# Controller.net
KiCad netlist of a schematic drawn in Altium Designer
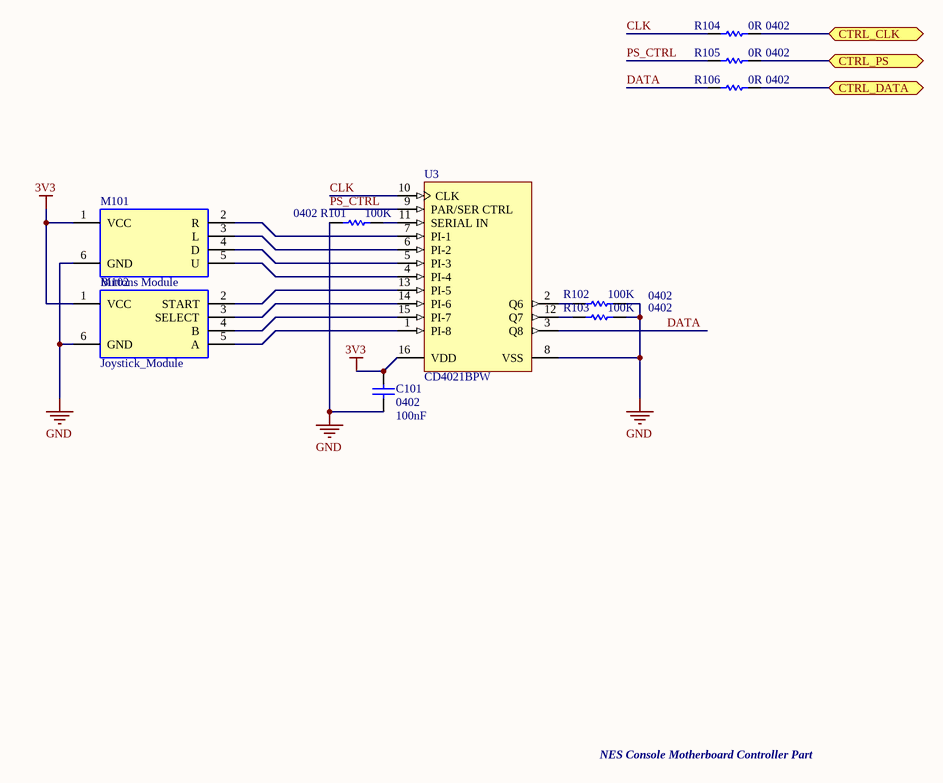
[diagram p0: Controller.SchDoc]

(export (version "E")
  (design (tool "Eeschema 10.0.6"))
  (components
    (comp (ref "C101")
      (value "0402")
      (footprint "CAPC1005X06N")
      (description "Capacitor")
      (fields (field (name "ALTIUM_VALUE") "100nF") (field (name "PUBLISHER") "Altium Limited"))
      (libsource (lib "Miscellaneous Devices") (part "Cap"))
    )
    (comp (ref "M101")
      (value "Buttons Module")
      (footprint "BUTTON_MODULE")
      (description "Controller Buttons Module")
      (libsource (lib "Schematic_Modules_NES") (part "Buttons Module"))
    )
    (comp (ref "M102")
      (value "Joystick_Module")
      (footprint "Joystick_Module")
      (description "Controller Joystick module")
      (libsource (lib "Schematic_Modules_NES") (part "Joystick Module"))
    )
    (comp (ref "R101")
      (value "0402")
      (footprint "RESC1005X04N")
      (description "Resistor")
      (fields (field (name "ALTIUM_VALUE") "100K") (field (name "PUBLISHER") "Altium Limited"))
      (libsource (lib "Miscellaneous Devices") (part "Res1"))
    )
    (comp (ref "R102")
      (value "0402")
      (footprint "RESC1005X04N")
      (description "Resistor")
      (fields (field (name "ALTIUM_VALUE") "100K") (field (name "PUBLISHER") "Altium Limited"))
      (libsource (lib "Miscellaneous Devices") (part "Res1"))
    )
    (comp (ref "R103")
      (value "0402")
      (footprint "RESC1005X04N")
      (description "Resistor")
      (fields (field (name "ALTIUM_VALUE") "100K") (field (name "PUBLISHER") "Altium Limited"))
      (libsource (lib "Miscellaneous Devices") (part "Res1"))
    )
    (comp (ref "R104")
      (value "0402")
      (footprint "RESC1005X04N")
      (description "Resistor")
      (fields (field (name "ALTIUM_VALUE") "0R") (field (name "PUBLISHER") "Altium Limited"))
      (libsource (lib "Miscellaneous Devices") (part "Res1"))
    )
    (comp (ref "R105")
      (value "0402")
      (footprint "RESC1005X04N")
      (description "Resistor")
      (fields (field (name "ALTIUM_VALUE") "0R") (field (name "PUBLISHER") "Altium Limited"))
      (libsource (lib "Miscellaneous Devices") (part "Res1"))
    )
    (comp (ref "R106")
      (value "0402")
      (footprint "RESC1005X04N")
      (description "Resistor")
      (fields (field (name "ALTIUM_VALUE") "0R") (field (name "PUBLISHER") "Altium Limited"))
      (libsource (lib "Miscellaneous Devices") (part "Res1"))
    )
    (comp (ref "U3")
      (value "CD4021BPW")
      (footprint "PW0016A_N")
      (description "CMOS 8-Stage Static Shift Register, PW0016A, TUBE")
      (fields
        (field (name "GENERIC PART NUMBER") "CD4021B")
        (field (name "MANUFACTURER") "Texas Instruments")
      )
      (libsource (lib "TI_Logic_Flip-Flop,Latch,Register") (part "CD4021BPW"))
    )
  )
  (nets
    (net (code "1") (name "/CLK") (class "Default")
      (node (ref "R104") (pin "2") (pinfunction "2_2") (pintype "passive"))
      (node (ref "U3") (pin "10") (pinfunction "CLK_10") (pintype "input"))
    )
    (net (code "2") (name "/CTRL_CLK") (class "Default")
      (node (ref "R104") (pin "1") (pinfunction "1_1") (pintype "passive"))
    )
    (net (code "3") (name "/CTRL_DATA") (class "Default")
      (node (ref "R106") (pin "1") (pinfunction "1_1") (pintype "passive"))
    )
    (net (code "4") (name "/CTRL_PS") (class "Default")
      (node (ref "R105") (pin "1") (pinfunction "1_1") (pintype "passive"))
    )
    (net (code "5") (name "/DATA") (class "Default")
      (node (ref "R106") (pin "2") (pinfunction "2_2") (pintype "passive"))
      (node (ref "U3") (pin "3") (pinfunction "Q8_3") (pintype "output"))
    )
    (net (code "6") (name "/PS_CTRL") (class "Default")
      (node (ref "R105") (pin "2") (pinfunction "2_2") (pintype "passive"))
      (node (ref "U3") (pin "9") (pinfunction "PAR/SER_CTRL_9") (pintype "input"))
    )
    (net (code "7") (name "3V3") (class "Default")
      (node (ref "C101") (pin "2") (pinfunction "2_2") (pintype "passive"))
      (node (ref "M101") (pin "1") (pinfunction "VCC_1") (pintype "passive"))
      (node (ref "M102") (pin "1") (pinfunction "VCC_1") (pintype "passive"))
      (node (ref "U3") (pin "16") (pinfunction "VDD_16") (pintype "power_in"))
    )
    (net (code "8") (name "GND") (class "Default")
      (node (ref "C101") (pin "1") (pinfunction "1_1") (pintype "passive"))
      (node (ref "M101") (pin "6") (pinfunction "GND_6") (pintype "passive"))
      (node (ref "M102") (pin "6") (pinfunction "GND_6") (pintype "passive"))
      (node (ref "R101") (pin "2") (pinfunction "2_2") (pintype "passive"))
      (node (ref "R102") (pin "1") (pinfunction "1_1") (pintype "passive"))
      (node (ref "R103") (pin "1") (pinfunction "1_1") (pintype "passive"))
      (node (ref "U3") (pin "8") (pinfunction "VSS_8") (pintype "power_in"))
    )
    (net (code "9") (name "Net-(M101-D)") (class "Default")
      (node (ref "M101") (pin "4") (pinfunction "D_4") (pintype "passive"))
      (node (ref "U3") (pin "5") (pinfunction "PI-3_5") (pintype "input"))
    )
    (net (code "10") (name "Net-(M101-L)") (class "Default")
      (node (ref "M101") (pin "3") (pinfunction "L_3") (pintype "passive"))
      (node (ref "U3") (pin "6") (pinfunction "PI-2_6") (pintype "input"))
    )
    (net (code "11") (name "Net-(M101-R)") (class "Default")
      (node (ref "M101") (pin "2") (pinfunction "R_2") (pintype "passive"))
      (node (ref "U3") (pin "7") (pinfunction "PI-1_7") (pintype "input"))
    )
    (net (code "12") (name "Net-(M101-U)") (class "Default")
      (node (ref "M101") (pin "5") (pinfunction "U_5") (pintype "passive"))
      (node (ref "U3") (pin "4") (pinfunction "PI-4_4") (pintype "input"))
    )
    (net (code "13") (name "Net-(M102-A)") (class "Default")
      (node (ref "M102") (pin "5") (pinfunction "A_5") (pintype "passive"))
      (node (ref "U3") (pin "1") (pinfunction "PI-8_1") (pintype "input"))
    )
    (net (code "14") (name "Net-(M102-B)") (class "Default")
      (node (ref "M102") (pin "4") (pinfunction "B_4") (pintype "passive"))
      (node (ref "U3") (pin "15") (pinfunction "PI-7_15") (pintype "input"))
    )
    (net (code "15") (name "Net-(M102-SELECT)") (class "Default")
      (node (ref "M102") (pin "3") (pinfunction "SELECT_3") (pintype "passive"))
      (node (ref "U3") (pin "14") (pinfunction "PI-6_14") (pintype "input"))
    )
    (net (code "16") (name "Net-(M102-START)") (class "Default")
      (node (ref "M102") (pin "2") (pinfunction "START_2") (pintype "passive"))
      (node (ref "U3") (pin "13") (pinfunction "PI-5_13") (pintype "input"))
    )
    (net (code "17") (name "Net-(U3-Q6)") (class "Default")
      (node (ref "R102") (pin "2") (pinfunction "2_2") (pintype "passive"))
      (node (ref "U3") (pin "2") (pinfunction "Q6_2") (pintype "output"))
    )
    (net (code "18") (name "Net-(U3-Q7)") (class "Default")
      (node (ref "R103") (pin "2") (pinfunction "2_2") (pintype "passive"))
      (node (ref "U3") (pin "12") (pinfunction "Q7_12") (pintype "output"))
    )
    (net (code "19") (name "Net-(U3-SERIAL_IN)") (class "Default")
      (node (ref "R101") (pin "1") (pinfunction "1_1") (pintype "passive"))
      (node (ref "U3") (pin "11") (pinfunction "SERIAL_IN_11") (pintype "input"))
    )
  )
)
